# 4V_DIST.net
KiCad netlist of a schematic drawn in Altium Designer
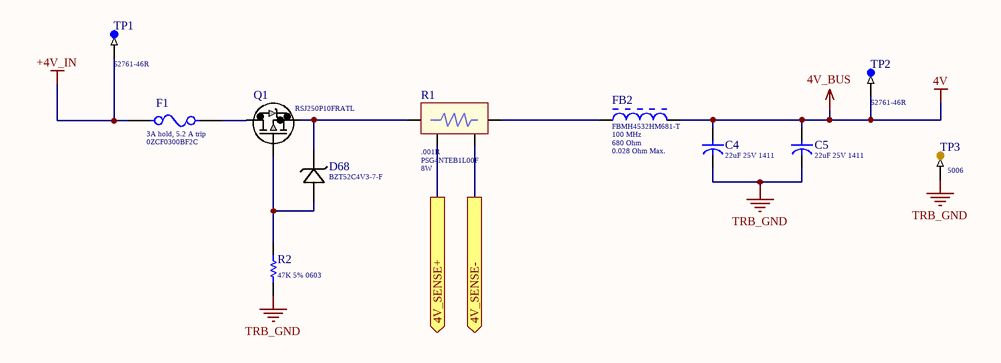
[diagram p0: 4V_DIST.SchDoc]

(export (version "E")
  (design (tool "Eeschema 10.0.6"))
  (components
    (comp (ref "C4")
      (value "Cap_Kemet_T521B226M025ATE100_22uF")
      (footprint "Cap_Kemet_T521B226M025ATE100_22uF")
      (description "Tantalum Capacitors - Polymer SMD 25V 22uF 1311 20% ESR=100mOhms")
      (fields (field (name "CAPACITANCE") "22uF 25V 1411"))
      (libsource (lib "Cap_Kemet_T521B226M025ATE100_22uF") (part "Cap_Kemet_T521B226M025ATE100_22uF"))
    )
    (comp (ref "C5")
      (value "Cap_Kemet_T521B226M025ATE100_22uF")
      (footprint "Cap_Kemet_T521B226M025ATE100_22uF")
      (description "Tantalum Capacitors - Polymer SMD 25V 22uF 1311 20% ESR=100mOhms")
      (fields (field (name "CAPACITANCE") "22uF 25V 1411"))
      (libsource (lib "Cap_Kemet_T521B226M025ATE100_22uF") (part "Cap_Kemet_T521B226M025ATE100_22uF"))
    )
    (comp (ref "D68")
      (value "BZT52C4V3-7-F")
      (footprint "SOD123")
      (description "Zener Diodes 500mW 4.3V Zener AEC-Q101 Qualified")
      (fields (field (name "SERIES") "BZT52C4V3-7-F"))
      (libsource (lib "4v3_zener_BZT52C4V3-7-F") (part "BZT52C4V3-7-F"))
    )
    (comp (ref "F1")
      (value "3A hold, 5.2 A trip")
      (footprint "Bel_0ZCF_MFG")
      (description "Resettable Fuses - PPTC 3A 24V PPTC 2920 SMD")
      (fields (field (name "SERIES") "0ZCF0300BF2C"))
      (libsource (lib "Fuse_Bel_0ZCF0300BF2C_3A_hold") (part "0ZCF0300BF2C"))
    )
    (comp (ref "FB2")
      (value "FBMH4532HM681-T")
      (footprint "TAYO-FBMH4532-2_V")
      (fields
        (field (name "PARTNUMBER") "FBMH4532HM681-T")
        (field (name "MANUFACTURER") "Taiyo Yuden")
        (field (name "MEASURING FREQUENCY") "100 MHz")
        (field (name "NOMINAL IMPEDANCE") "680 Ohm")
        (field (name "DC RESISTANCE") "0.028 Ohm Max.")
      )
      (libsource (lib "Taiyo_Yuden_FBMH4532HM681") (part "FBMH4532HM681-T"))
    )
    (comp (ref "Q1")
      (value "Mos_ROHM_RSJ250P10FRATL_25A")
      (footprint "Mos_ROHM_RSJ250P10FRATL_25A")
      (description "MOSFET Pch -100V Vds -25A 0.05Rds(on) 60Qg")
      (fields (field (name "SERIES") "RSJ250P10FRATL"))
      (libsource (lib "Mos_ROHM_RSJ250P10FRATL_25A") (part "Mos_ROHM_RSJ250P10FRATL_25A"))
    )
    (comp (ref "R1")
      (value "SRes_KOA_PSG4NTEB1L00F_1mOhm")
      (footprint "SRes_KOA_PSG4NTEB1L00F_1mOhm")
      (description "Current Sense Resistors - SMD 1mOhm 8W 1% 50ppm AEC-Q200 Power Shunt")
      (fields
        (field (name "RESISTANCE") ".001R")
        (field (name "SERIES") "PSG4NTEB1L00F")
        (field (name "PARAMETER 1") "8W")
      )
      (libsource (lib "SRes_KOA_PSG4NTEB1L00F_1mOhm") (part "SRes_KOA_PSG4NTEB1L00F_1mOhm"))
    )
    (comp (ref "R2")
      (value "47K 5% 0603")
      (footprint "RESC0603(1608)_L")
      (description "47K 0.1W 5% 0603 (1608 Metric)  SMD")
      (fields (field (name "TOLERANCE") "5 %") (field (name "POWER") "0.1 W"))
      (libsource (lib "Altium Content Vault") (part "RES"))
    )
    (comp (ref "TP1")
      (value "TP_Harwin_S2761_46R")
      (footprint "TP_Harwin_S2761_46R")
      (description "Circuit Board Hardware - PCB SMT Mini Test Terminal, Reel")
      (fields (field (name "SERIES") "S2761-46R"))
      (libsource (lib "TP_Harwin_S2761_46R") (part "TP_Harwin_S2761_46R"))
    )
    (comp (ref "TP2")
      (value "TP_Harwin_S2761_46R")
      (footprint "TP_Harwin_S2761_46R")
      (description "Circuit Board Hardware - PCB SMT Mini Test Terminal, Reel")
      (fields (field (name "SERIES") "S2761-46R"))
      (libsource (lib "TP_Harwin_S2761_46R") (part "TP_Harwin_S2761_46R"))
    )
    (comp (ref "TP3")
      (value "TP_Keystone_Electronics_5006")
      (footprint "TP_Keystone_Electronics_5006")
      (description "Circuit Board Hardware - PCB TEST POINT BLK .063")
      (fields (field (name "SERIES") "5006"))
      (libsource (lib "TP_Keystone_Electronics_5006") (part "TP_Keystone_Electronics_5006"))
    )
  )
  (nets
    (net (code "1") (name "+4V_IN") (class "Default")
      (node (ref "F1") (pin "1") (pinfunction "1_1") (pintype "passive"))
      (node (ref "TP1") (pin "1") (pinfunction "1_1") (pintype "input"))
    )
    (net (code "2") (name "/4V_SENSE+") (class "Default")
      (node (ref "R1") (pin "4") (pinfunction "4_4") (pintype "passive"))
    )
    (net (code "3") (name "/4V_SENSE-") (class "Default")
      (node (ref "R1") (pin "3") (pinfunction "3_3") (pintype "passive"))
    )
    (net (code "4") (name "4V") (class "Default")
      (node (ref "C4") (pin "1") (pinfunction "1_1") (pintype "passive"))
      (node (ref "C5") (pin "1") (pinfunction "1_1") (pintype "passive"))
      (node (ref "FB2") (pin "2") (pinfunction "2_2") (pintype "passive"))
      (node (ref "TP2") (pin "1") (pinfunction "1_1") (pintype "input"))
    )
    (net (code "5") (name "Net-(FB2-Pad1)") (class "Default")
      (node (ref "FB2") (pin "1") (pinfunction "1_1") (pintype "passive"))
      (node (ref "R1") (pin "2") (pinfunction "2_2") (pintype "passive"))
    )
    (net (code "6") (name "Net-(Q1-D)") (class "Default")
      (node (ref "F1") (pin "2") (pinfunction "2_2") (pintype "passive"))
      (node (ref "Q1") (pin "2") (pinfunction "D_2") (pintype "passive"))
    )
    (net (code "7") (name "Net-(Q1-G)") (class "Default")
      (node (ref "D68") (pin "2") (pinfunction "2_2") (pintype "passive"))
      (node (ref "Q1") (pin "1") (pinfunction "G_1") (pintype "passive"))
      (node (ref "R2") (pin "2") (pinfunction "2_2") (pintype "passive"))
    )
    (net (code "8") (name "Net-(Q1-S)") (class "Default")
      (node (ref "D68") (pin "1") (pinfunction "1_1") (pintype "passive"))
      (node (ref "Q1") (pin "3") (pinfunction "S_3") (pintype "passive"))
      (node (ref "R1") (pin "1") (pinfunction "1_1") (pintype "passive"))
    )
    (net (code "9") (name "TRB_GND") (class "Default")
      (node (ref "C4") (pin "2") (pinfunction "2_2") (pintype "passive"))
      (node (ref "C5") (pin "2") (pinfunction "2_2") (pintype "passive"))
      (node (ref "R2") (pin "1") (pinfunction "1_1") (pintype "passive"))
      (node (ref "TP3") (pin "1") (pinfunction "1_1") (pintype "input"))
    )
  )
)
